# inputs.net
KiCad netlist of a schematic drawn in Altium Designer
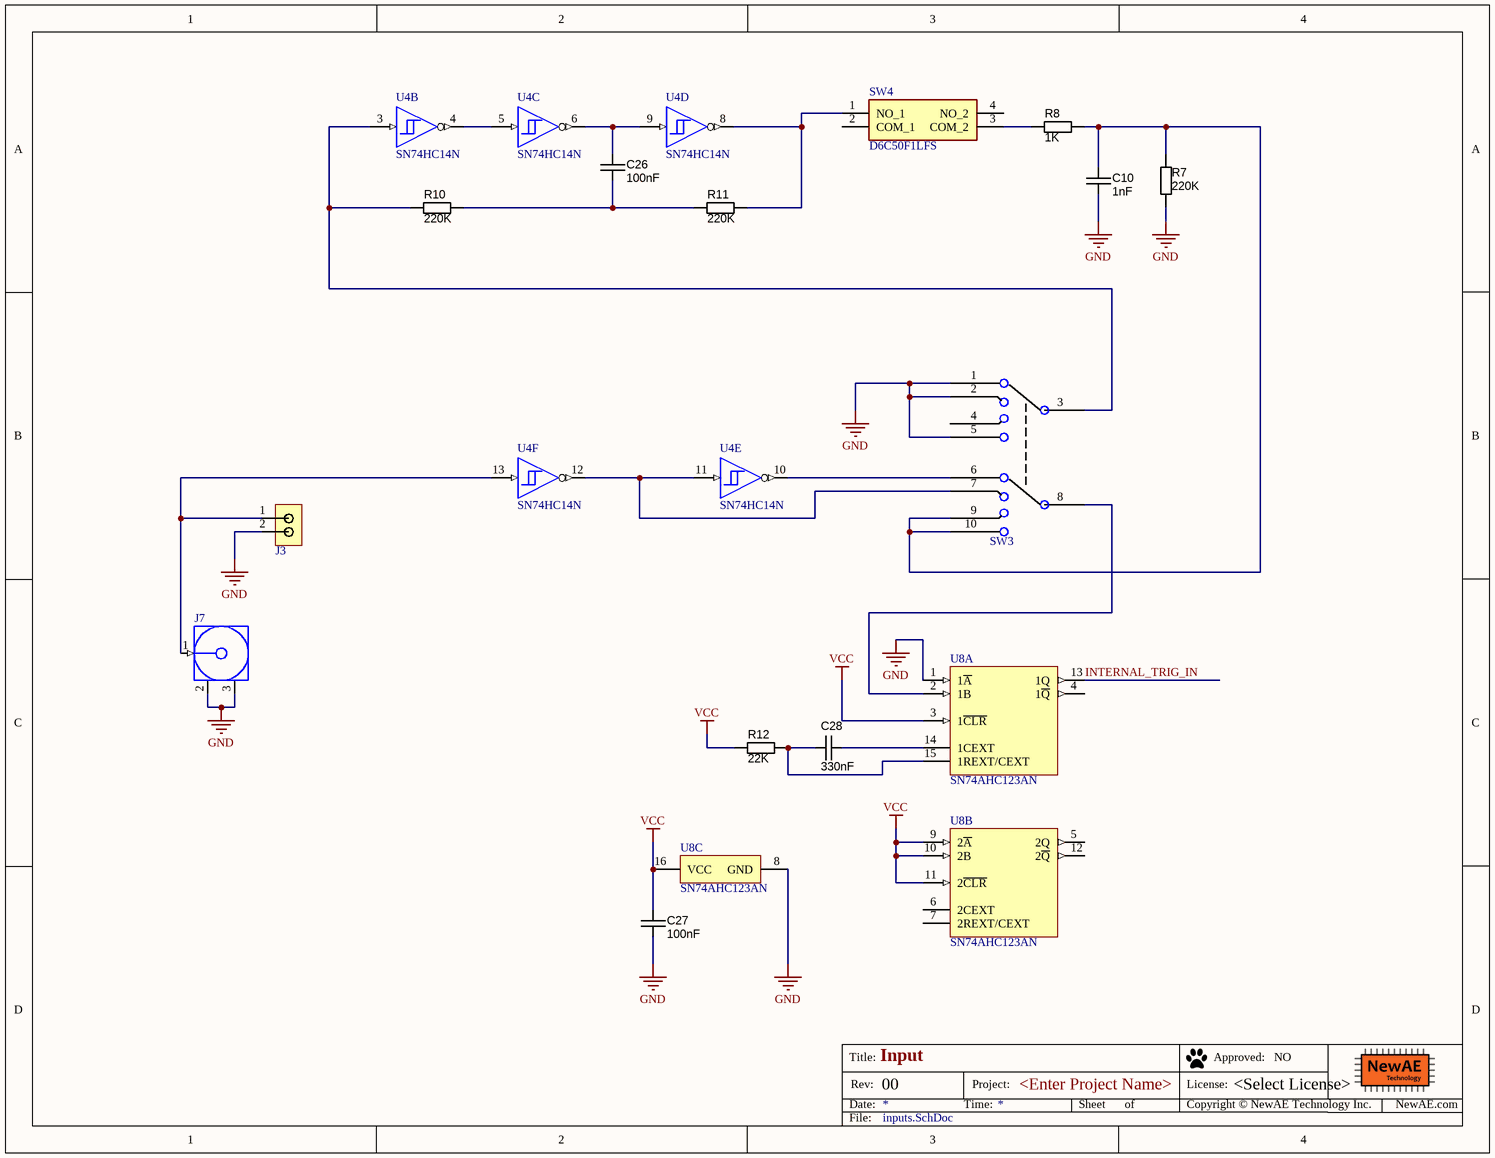
[diagram p0: inputs.SchDoc]

(export (version "E")
  (design (tool "Eeschema 10.0.6"))
  (components
    (comp (ref "C10")
      (value "1nF")
      (footprint "CAPC500P450250X550")
      (description "Capacitor Ceramic 220nF 10% 50V X7R radial 5mm lead spacing")
      (fields (field (name "TOLERANCE") "±10%") (field (name "Comment") "approved sub OK"))
      (libsource (lib "PBL - Capacitors") (part "CAPR_220n_Radial_5mm"))
    )
    (comp (ref "C26")
      (value "100nF")
      (footprint "CAPC500P450250X550")
      (description "Capacitor Ceramic 220nF 10% 50V X7R radial 5mm lead spacing")
      (fields (field (name "TOLERANCE") "±10%") (field (name "Comment") "approved sub OK"))
      (libsource (lib "PBL - Capacitors") (part "CAPR_220n_Radial_5mm"))
    )
    (comp (ref "C27")
      (value "100nF")
      (footprint "CAPC500P450250X550")
      (description "Capacitor Ceramic 220nF 10% 50V X7R radial 5mm lead spacing")
      (fields (field (name "TOLERANCE") "±10%") (field (name "Comment") "approved sub OK"))
      (libsource (lib "PBL - Capacitors") (part "CAPR_220n_Radial_5mm"))
    )
    (comp (ref "C28")
      (value "330nF")
      (footprint "CAPC500P450250X550")
      (description "Capacitor Ceramic 220nF 10% 50V X7R radial 5mm lead spacing")
      (fields (field (name "TOLERANCE") "±10%") (field (name "Comment") "approved sub OK"))
      (libsource (lib "PBL - Capacitors") (part "CAPR_220n_Radial_5mm"))
    )
    (comp (ref "J3")
      (value "Jumper")
      (footprint "2x2.54mm_Header")
      (description "1x2 2.54mm header, male pins")
      (fields (field (name "PART NUMBER") "2_PIN_JUMPER"))
      (libsource (lib "NewAE_AltiumLib") (part "1x2_Pin_Header"))
    )
    (comp (ref "J7")
      (value "73171-3150")
      (footprint "73171-3150")
      (description "Molex Cheap R/A BNC")
      (fields (field (name "PART NUMBER") "CON-BNC-CHEAP"))
      (libsource (lib "NewAE_AltiumLib") (part "CON-RF-2GND"))
    )
    (comp (ref "R7")
      (value "220K")
      (footprint "RESTH_AXIAL-0.4")
      (description "Resistor THD Axial 220 Ohm 0.25W 5% Carbon Film")
      (fields (field (name "TOLERANCE") "±5%") (field (name "Comment") "Carbon Film"))
      (libsource (lib "") (part "RES_220R_Axial_0.25W_5%_2"))
    )
    (comp (ref "R8")
      (value "1K")
      (footprint "RESTH_AXIAL-0.4")
      (description "Resistor THD Axial 220 Ohm 0.25W 5% Carbon Film")
      (fields (field (name "TOLERANCE") "±5%") (field (name "Comment") "Carbon Film"))
      (libsource (lib "") (part "RES_220R_Axial_0.25W_5%_1"))
    )
    (comp (ref "R10")
      (value "220K")
      (footprint "RESTH_AXIAL-0.4")
      (description "Resistor THD Axial 220 Ohm 0.25W 5% Carbon Film")
      (fields (field (name "TOLERANCE") "±5%") (field (name "Comment") "Carbon Film"))
      (libsource (lib "PBL - Resistors") (part "RES_220R_Axial_0.25W_5%"))
    )
    (comp (ref "R11")
      (value "220K")
      (footprint "RESTH_AXIAL-0.4")
      (description "Resistor THD Axial 220 Ohm 0.25W 5% Carbon Film")
      (fields (field (name "TOLERANCE") "±5%") (field (name "Comment") "Carbon Film"))
      (libsource (lib "PBL - Resistors") (part "RES_220R_Axial_0.25W_5%"))
    )
    (comp (ref "R12")
      (value "22K")
      (footprint "RESTH_AXIAL-0.4")
      (description "Resistor THD Axial 220 Ohm 0.25W 5% Carbon Film")
      (fields (field (name "TOLERANCE") "±5%") (field (name "Comment") "Carbon Film"))
      (libsource (lib "PBL - Resistors") (part "RES_220R_Axial_0.25W_5%"))
    )
    (comp (ref "SW3")
      (value "SS-24E06-TG 5 (P)")
      (footprint "CK_SS24E06TG5P")
      (description "2P4T Slide, C&K Through Hole")
      (fields (field (name "PART NUMBER") "SS24E06TG5P"))
      (libsource (lib "NewAE_AltiumLib") (part "SW_2P4T_SS24E06TG5P"))
    )
    (comp (ref "SW4")
      (value "D6C50F1LFS")
      (footprint "SamacSys:D6C50F1LFS")
      (description "Switch")
      (fields (field (name "MOUSER PART NUMBER") "611-D6C50F1LFS"))
      (libsource (lib "*") (part "D6C50F1LFS"))
    )
    (comp (ref "U4")
      (value "SN74HC14N")
      (footprint "N0014A")
      (description "Hex Schmitt-Trigger Inverters, N0014A, TUBE")
      (fields
        (field (name "MANUFACTURER") "Texas Instruments")
        (field (name "GENERIC PART NUMBER") "SN74HC14")
      )
      (libsource (lib "Altium Content Vault") (part "TI-CD_SNX4XXXXXX4X_19A-14-SCHMITT"))
    )
    (comp (ref "U8")
      (value "SN74AHC123AN")
      (footprint "N0016A")
      (description "Dual Retriggerable Monostable Multivibrators, N0016A, TUBE")
      (fields
        (field (name "GENERIC PART NUMBER") "SN74AHC123A")
        (field (name "MANUFACTURER") "Texas Instruments")
      )
      (libsource (lib "Altium Content Vault") (part "TI-SNX4XXXX123A_74LV221A-16"))
    )
  )
  (nets
    (net (code "1") (name "/INTERNAL_TRIG_IN") (class "Default")
      (node (ref "U8") (pin "13") (pinfunction "1Q_13") (pintype "output"))
    )
    (net (code "2") (name "GND") (class "Default")
      (node (ref "C10") (pin "1") (pintype "passive"))
      (node (ref "C27") (pin "2") (pintype "passive"))
      (node (ref "J3") (pin "2") (pinfunction "2_2") (pintype "passive"))
      (node (ref "J7") (pin "2") (pinfunction "GND_2") (pintype "power_in"))
      (node (ref "J7") (pin "3") (pinfunction "GND_3") (pintype "power_in"))
      (node (ref "R7") (pin "1") (pinfunction "1_1") (pintype "passive"))
      (node (ref "SW3") (pin "1") (pinfunction "1_1") (pintype "passive"))
      (node (ref "SW3") (pin "2") (pinfunction "2_2") (pintype "passive"))
      (node (ref "SW3") (pin "5") (pinfunction "5_5") (pintype "passive"))
      (node (ref "U8") (pin "1") (pinfunction "1~{A}_1") (pintype "input"))
      (node (ref "U8") (pin "8") (pinfunction "GND_8") (pintype "power_in"))
    )
    (net (code "3") (name "Net-(C10-Pad2)") (class "Default")
      (node (ref "C10") (pin "2") (pintype "passive"))
      (node (ref "R7") (pin "2") (pinfunction "2_2") (pintype "passive"))
      (node (ref "R8") (pin "2") (pinfunction "2_2") (pintype "passive"))
      (node (ref "SW3") (pin "10") (pinfunction "10_10") (pintype "passive"))
      (node (ref "SW3") (pin "9") (pinfunction "9_9") (pintype "passive"))
    )
    (net (code "4") (name "Net-(C26-Pad2)") (class "Default")
      (node (ref "C26") (pin "2") (pintype "passive"))
      (node (ref "R10") (pin "1") (pinfunction "1_1") (pintype "passive"))
      (node (ref "R11") (pin "2") (pinfunction "2_2") (pintype "passive"))
    )
    (net (code "5") (name "Net-(J7-Signal)") (class "Default")
      (node (ref "J3") (pin "1") (pinfunction "1_1") (pintype "passive"))
      (node (ref "J7") (pin "1") (pinfunction "Signal_1") (pintype "input"))
      (node (ref "U4") (pin "13") (pinfunction "6A_13") (pintype "input"))
    )
    (net (code "6") (name "Net-(SW4-COM_2)") (class "Default")
      (node (ref "R8") (pin "1") (pinfunction "1_1") (pintype "passive"))
      (node (ref "SW4") (pin "3") (pinfunction "COM_2_3") (pintype "passive"))
    )
    (net (code "7") (name "Net-(SW4-NO_1)") (class "Default")
      (node (ref "R11") (pin "1") (pinfunction "1_1") (pintype "passive"))
      (node (ref "SW4") (pin "1") (pinfunction "NO_1_1") (pintype "passive"))
      (node (ref "U4") (pin "8") (pinfunction "~{4Y}_8") (pintype "output"))
    )
    (net (code "8") (name "Net-(U4B-2A)") (class "Default")
      (node (ref "R10") (pin "2") (pinfunction "2_2") (pintype "passive"))
      (node (ref "SW3") (pin "3") (pinfunction "3_3") (pintype "passive"))
      (node (ref "U4") (pin "3") (pinfunction "2A_3") (pintype "input"))
    )
    (net (code "9") (name "Net-(U4B-~{2Y})") (class "Default")
      (node (ref "U4") (pin "4") (pinfunction "~{2Y}_4") (pintype "output"))
      (node (ref "U4") (pin "5") (pinfunction "3A_5") (pintype "input"))
    )
    (net (code "10") (name "Net-(U4C-~{3Y})") (class "Default")
      (node (ref "C26") (pin "1") (pintype "passive"))
      (node (ref "U4") (pin "6") (pinfunction "~{3Y}_6") (pintype "output"))
      (node (ref "U4") (pin "9") (pinfunction "4A_9") (pintype "input"))
    )
    (net (code "11") (name "Net-(U4E-5A)") (class "Default")
      (node (ref "SW3") (pin "7") (pinfunction "7_7") (pintype "passive"))
      (node (ref "U4") (pin "11") (pinfunction "5A_11") (pintype "input"))
      (node (ref "U4") (pin "12") (pinfunction "~{6Y}_12") (pintype "output"))
    )
    (net (code "12") (name "Net-(U4E-~{5Y})") (class "Default")
      (node (ref "SW3") (pin "6") (pinfunction "6_6") (pintype "passive"))
      (node (ref "U4") (pin "10") (pinfunction "~{5Y}_10") (pintype "output"))
    )
    (net (code "13") (name "Net-(U8A-1B)") (class "Default")
      (node (ref "SW3") (pin "8") (pinfunction "8_8") (pintype "passive"))
      (node (ref "U8") (pin "2") (pinfunction "1B_2") (pintype "input"))
    )
    (net (code "14") (name "Net-(U8A-1CEXT)") (class "Default")
      (node (ref "C28") (pin "2") (pintype "passive"))
      (node (ref "U8") (pin "14") (pinfunction "1CEXT_14") (pintype "passive"))
    )
    (net (code "15") (name "Net-(U8A-1REXT{slash}CEXT)") (class "Default")
      (node (ref "C28") (pin "1") (pintype "passive"))
      (node (ref "R12") (pin "1") (pinfunction "1_1") (pintype "passive"))
      (node (ref "U8") (pin "15") (pinfunction "1REXT/CEXT_15") (pintype "passive"))
    )
    (net (code "16") (name "VCC") (class "Default")
      (node (ref "C27") (pin "1") (pintype "passive"))
      (node (ref "R12") (pin "2") (pinfunction "2_2") (pintype "passive"))
      (node (ref "U8") (pin "10") (pinfunction "2B_10") (pintype "input"))
      (node (ref "U8") (pin "11") (pinfunction "2~{CLR}_11") (pintype "input"))
      (node (ref "U8") (pin "16") (pinfunction "VCC_16") (pintype "power_in"))
      (node (ref "U8") (pin "3") (pinfunction "1~{CLR}_3") (pintype "input"))
      (node (ref "U8") (pin "9") (pinfunction "2~{A}_9") (pintype "input"))
    )
    (net (code "17") (name "unconnected-(SW3-Pad4)") (class "Default")
      (node (ref "SW3") (pin "4") (pinfunction "4_4") (pintype "passive"))
    )
    (net (code "18") (name "unconnected-(SW4-COM_1-Pad2)") (class "Default")
      (node (ref "SW4") (pin "2") (pinfunction "COM_1_2") (pintype "passive"))
    )
    (net (code "19") (name "unconnected-(SW4-NO_2-Pad4)") (class "Default")
      (node (ref "SW4") (pin "4") (pinfunction "NO_2_4") (pintype "passive"))
    )
    (net (code "20") (name "unconnected-(U8A-1~{Q}-Pad4)") (class "Default")
      (node (ref "U8") (pin "4") (pinfunction "1~{Q}_4") (pintype "output"))
    )
    (net (code "21") (name "unconnected-(U8B-2CEXT-Pad6)") (class "Default")
      (node (ref "U8") (pin "6") (pinfunction "2CEXT_6") (pintype "passive"))
    )
    (net (code "22") (name "unconnected-(U8B-2Q-Pad5)") (class "Default")
      (node (ref "U8") (pin "5") (pinfunction "2Q_5") (pintype "output"))
    )
    (net (code "23") (name "unconnected-(U8B-2REXT{slash}CEXT-Pad7)") (class "Default")
      (node (ref "U8") (pin "7") (pinfunction "2REXT/CEXT_7") (pintype "passive"))
    )
    (net (code "24") (name "unconnected-(U8B-2~{Q}-Pad12)") (class "Default")
      (node (ref "U8") (pin "12") (pinfunction "2~{Q}_12") (pintype "output"))
    )
  )
)
